# hexcooler_v1.net
KiCad netlist of a schematic drawn in EasyEDA Pro
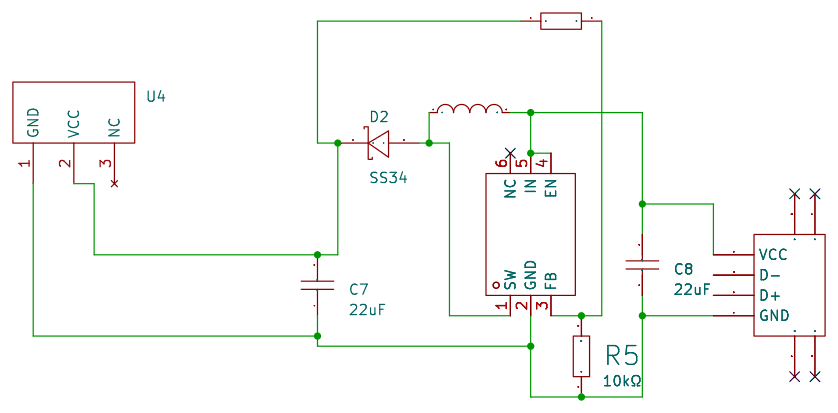
[diagram p0: schematic sheet]

(export (version "E")
  (design (tool "Eeschema 10.0.6"))
  (components
    (comp (ref "C7")
      (value "22uF")
      (footprint "easyedapro:C1206")
      (description "Capacitance:22uF Tolerance:±10% Tolerance:±10% Voltage Rating:25V Temperature Coefficient:X5R")
      (fields
        (field (name "Manufacturer Part") "CL31A226KAHNNNE")
        (field (name "Manufacturer") "SAMSUNG(三星)")
      )
      (libsource (lib "easyedapro") (part "CL31A226KAHNNNE"))
    )
    (comp (ref "C8")
      (value "22uF")
      (footprint "easyedapro:C1206")
      (description "Capacitance:22uF Tolerance:±10% Tolerance:±10% Voltage Rating:25V Temperature Coefficient:X5R")
      (fields
        (field (name "Manufacturer Part") "CL31A226KAHNNNE")
        (field (name "Manufacturer") "SAMSUNG(三星)")
      )
      (libsource (lib "easyedapro") (part "CL31A226KAHNNNE"))
    )
    (comp (ref "D2")
      (value "SS34")
      (footprint "easyedapro:SMA_L4.3-W2.6-LS5.2-RD")
      (fields (field (name "Manufacturer") "MDD(辰达半导体)"))
      (libsource (lib "easyedapro") (part "SS34_C8678"))
    )
    (comp (ref "L1")
      (value "4.7uH")
      (footprint "easyedapro:IND-SMD_L3.0-W3.0_LQH3NPN2R2NG0L")
      (fields (field (name "Manufacturer Part") "LQH3NPN4R7MJRL") (field (name "Manufacturer") "muRata(村田)"))
      (libsource (lib "easyedapro") (part "LQH3NPN4R7MJRL"))
    )
    (comp (ref "R3")
      (value "200kΩ")
      (footprint "easyedapro:R0805")
      (fields
        (field (name "Manufacturer Part") "0805W8F2003T5E")
        (field (name "Manufacturer") "UNI-ROYAL(厚声)")
      )
      (libsource (lib "easyedapro") (part "0805W8F2003T5E"))
    )
    (comp (ref "R5")
      (value "10kΩ")
      (footprint "easyedapro:R0603")
      (fields
        (field (name "Manufacturer Part") "0603WAF1002T5E")
        (field (name "Manufacturer") "UNI-ROYAL(厚声)")
      )
      (libsource (lib "easyedapro") (part "0603WAF1002T5E"))
    )
    (comp (ref "U3")
      (value "MT3608")
      (footprint "easyedapro:SOT-23-6_L2.9-W1.6-P0.95-LS2.8-BL")
      (fields (field (name "Manufacturer") "西安航天民芯"))
      (libsource (lib "easyedapro") (part "MT3608"))
    )
    (comp (ref "U4")
      (value "~")
      (footprint "easyedapro:pads junction")
      (libsource (lib "easyedapro") (part "connector for m y fan"))
    )
    (comp (ref "USB6")
      (value "911-321B2028S10100")
      (footprint "easyedapro:USB-A-SMD_911-321B2028S10100")
      (fields (field (name "Manufacturer") "精拓金"))
      (libsource (lib "easyedapro") (part "A/FPaste board Dparagraph10Four feet without curling ironLCPVinyl6.8Reverse"))
    )
  )
  (nets
    (net (code "1") (name "Net-(D2-A)") (class "Default")
      (node (ref "D2") (pin "2") (pinfunction "A_2") (pintype "unspecified"))
      (node (ref "L1") (pin "1") (pinfunction "1_1") (pintype "unspecified"))
      (node (ref "U3") (pin "1") (pinfunction "SW_1") (pintype "unspecified"))
    )
    (net (code "2") (name "Net-(D2-K)") (class "Default")
      (node (ref "C7") (pin "2") (pinfunction "2_2") (pintype "input"))
      (node (ref "D2") (pin "1") (pinfunction "K_1") (pintype "unspecified"))
      (node (ref "R3") (pin "1") (pinfunction "1_1") (pintype "input"))
      (node (ref "U4") (pin "2") (pinfunction "VCC_2") (pintype "input"))
    )
    (net (code "3") (name "Net-(U3-EN)") (class "Default")
      (node (ref "C8") (pin "2") (pinfunction "2_2") (pintype "input"))
      (node (ref "L1") (pin "2") (pinfunction "2_2") (pintype "unspecified"))
      (node (ref "U3") (pin "4") (pinfunction "EN_4") (pintype "unspecified"))
      (node (ref "U3") (pin "5") (pinfunction "IN_5") (pintype "unspecified"))
      (node (ref "USB6") (pin "1") (pinfunction "VCC_1") (pintype "input"))
    )
    (net (code "4") (name "Net-(U3-FB)") (class "Default")
      (node (ref "R3") (pin "2") (pinfunction "2_2") (pintype "input"))
      (node (ref "R5") (pin "2") (pinfunction "2_2") (pintype "input"))
      (node (ref "U3") (pin "3") (pinfunction "FB_3") (pintype "unspecified"))
    )
    (net (code "5") (name "Net-(U3-GND)") (class "Default")
      (node (ref "C7") (pin "1") (pinfunction "1_1") (pintype "input"))
      (node (ref "C8") (pin "1") (pinfunction "1_1") (pintype "input"))
      (node (ref "R5") (pin "1") (pinfunction "1_1") (pintype "input"))
      (node (ref "U3") (pin "2") (pinfunction "GND_2") (pintype "unspecified"))
      (node (ref "U4") (pin "1") (pinfunction "GND_1") (pintype "input"))
      (node (ref "USB6") (pin "4") (pinfunction "GND_4") (pintype "input"))
    )
    (net (code "6") (name "unconnected-(U3-NC-Pad6)") (class "Default")
      (node (ref "U3") (pin "6") (pinfunction "NC_6") (pintype "unspecified+no_connect"))
    )
    (net (code "7") (name "unconnected-(U4-NC-Pad3)") (class "Default")
      (node (ref "U4") (pin "3") (pinfunction "NC_3") (pintype "no_connect"))
    )
    (net (code "8") (name "unconnected-(USB6-1-Pad6)") (class "Default")
      (node (ref "USB6") (pin "6") (pinfunction "1_6") (pintype "unspecified+no_connect"))
    )
    (net (code "9") (name "unconnected-(USB6-2-Pad7)") (class "Default")
      (node (ref "USB6") (pin "7") (pinfunction "2_7") (pintype "unspecified+no_connect"))
    )
    (net (code "10") (name "unconnected-(USB6-3-Pad8)") (class "Default")
      (node (ref "USB6") (pin "8") (pinfunction "3_8") (pintype "unspecified+no_connect"))
    )
    (net (code "11") (name "unconnected-(USB6-D+-Pad3)") (class "Default")
      (node (ref "USB6") (pin "3") (pinfunction "D+_3") (pintype "input"))
    )
    (net (code "12") (name "unconnected-(USB6-D--Pad2)") (class "Default")
      (node (ref "USB6") (pin "2") (pinfunction "D-_2") (pintype "input"))
    )
    (net (code "13") (name "unconnected-(USB6-Pad5)") (class "Default")
      (node (ref "USB6") (pin "5") (pinfunction "5_5") (pintype "unspecified+no_connect"))
    )
  )
)
